# Multiplexer_8_to_1.net
KiCad netlist of a schematic drawn in Altium Designer
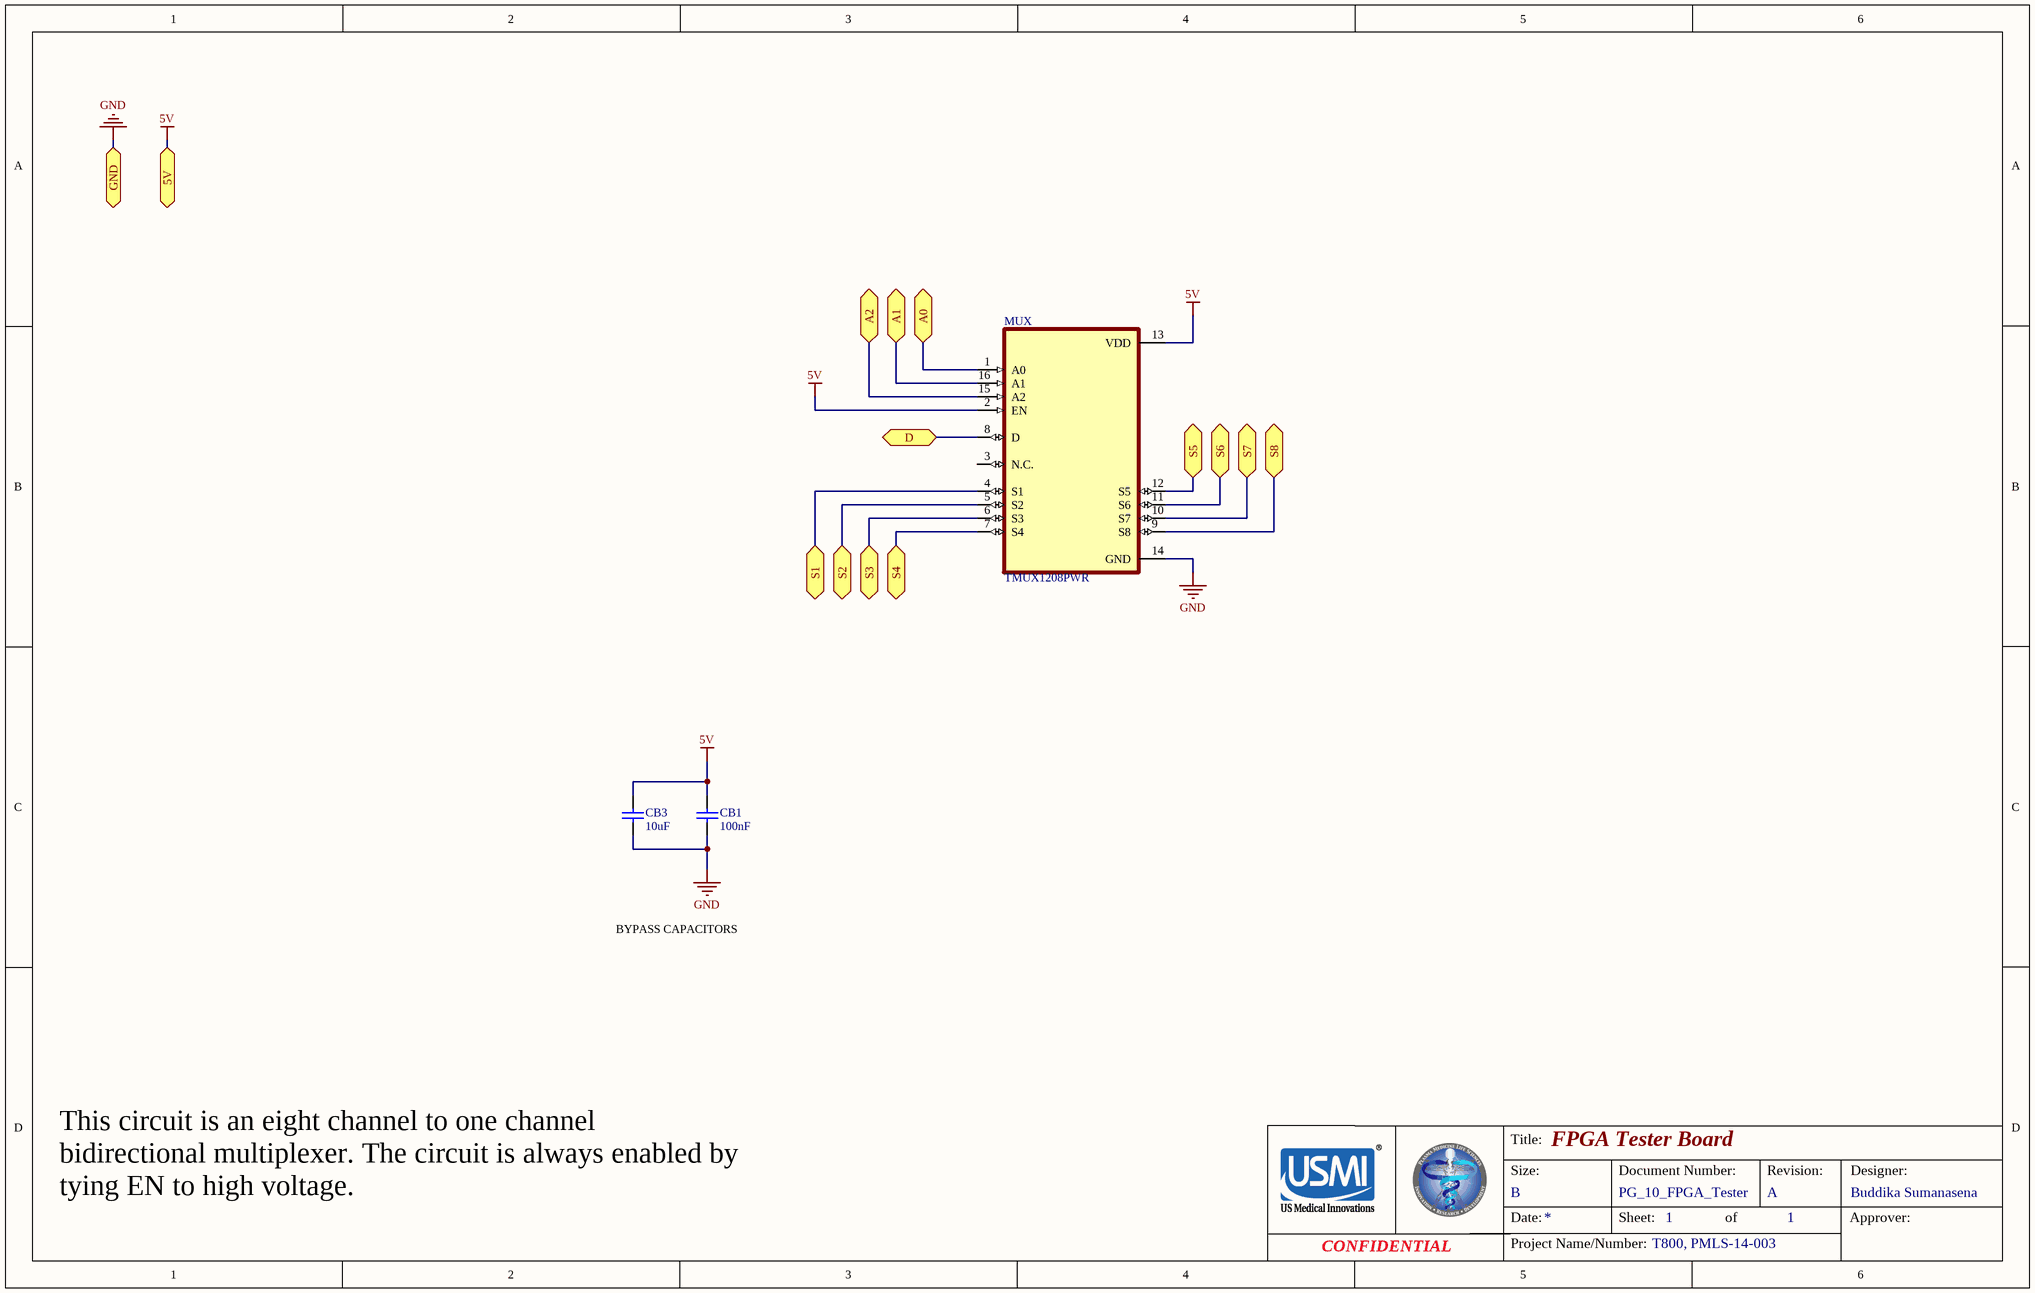
[diagram p0: Multiplexer_8_to_1.SchDoc]

(export (version "E")
  (design (tool "Eeschema 10.0.6"))
  (components
    (comp (ref "CB1")
      (value "100nF")
      (footprint "0805c")
      (description "Capacitor")
      (fields (field (name "PUBLISHER") "Altium Limited"))
      (libsource (lib "Buddika Miscellaneous Devices") (part "Cap"))
    )
    (comp (ref "CB3")
      (value "10uF")
      (footprint "1206c")
      (description "Capacitor")
      (fields (field (name "PUBLISHER") "Altium Limited"))
      (libsource (lib "Buddika Miscellaneous Devices") (part "Cap"))
    )
    (comp (ref "MUX")
      (value "TMUX1208PWR")
      (footprint "SOP65P640X120-16N")
      (description "5-V, 8:1, 1-channel general-purpose analog multiplexer with 1.8-V input logic 16-TSSOP -40 to 125")
      (fields (field (name "MF") "Texas Instruments"))
      (libsource (lib "TMUX1208PWR") (part "TMUX1208PWR"))
    )
  )
  (nets
    (net (code "1") (name "/A0") (class "Default")
      (node (ref "MUX") (pin "1") (pinfunction "A0_1") (pintype "input"))
    )
    (net (code "2") (name "/A1") (class "Default")
      (node (ref "MUX") (pin "16") (pinfunction "A1_16") (pintype "input"))
    )
    (net (code "3") (name "/A2") (class "Default")
      (node (ref "MUX") (pin "15") (pinfunction "A2_15") (pintype "input"))
    )
    (net (code "4") (name "/D") (class "Default")
      (node (ref "MUX") (pin "8") (pinfunction "D_8") (pintype "bidirectional"))
    )
    (net (code "5") (name "/S1") (class "Default")
      (node (ref "MUX") (pin "4") (pinfunction "S1_4") (pintype "bidirectional"))
    )
    (net (code "6") (name "/S2") (class "Default")
      (node (ref "MUX") (pin "5") (pinfunction "S2_5") (pintype "bidirectional"))
    )
    (net (code "7") (name "/S3") (class "Default")
      (node (ref "MUX") (pin "6") (pinfunction "S3_6") (pintype "bidirectional"))
    )
    (net (code "8") (name "/S4") (class "Default")
      (node (ref "MUX") (pin "7") (pinfunction "S4_7") (pintype "bidirectional"))
    )
    (net (code "9") (name "/S5") (class "Default")
      (node (ref "MUX") (pin "12") (pinfunction "S5_12") (pintype "bidirectional"))
    )
    (net (code "10") (name "/S6") (class "Default")
      (node (ref "MUX") (pin "11") (pinfunction "S6_11") (pintype "bidirectional"))
    )
    (net (code "11") (name "/S7") (class "Default")
      (node (ref "MUX") (pin "10") (pinfunction "S7_10") (pintype "bidirectional"))
    )
    (net (code "12") (name "/S8") (class "Default")
      (node (ref "MUX") (pin "9") (pinfunction "S8_9") (pintype "bidirectional"))
    )
    (net (code "13") (name "5V") (class "Default")
      (node (ref "CB1") (pin "2") (pinfunction "2_2") (pintype "passive"))
      (node (ref "CB3") (pin "2") (pinfunction "2_2") (pintype "passive"))
      (node (ref "MUX") (pin "13") (pinfunction "VDD_13") (pintype "power_in"))
      (node (ref "MUX") (pin "2") (pinfunction "EN_2") (pintype "input"))
    )
    (net (code "14") (name "GND") (class "Default")
      (node (ref "CB1") (pin "1") (pinfunction "1_1") (pintype "passive"))
      (node (ref "CB3") (pin "1") (pinfunction "1_1") (pintype "passive"))
      (node (ref "MUX") (pin "14") (pinfunction "GND_14") (pintype "power_in"))
    )
    (net (code "15") (name "unconnected-(MUX-N.C.-Pad3)") (class "Default")
      (node (ref "MUX") (pin "3") (pinfunction "N.C._3") (pintype "bidirectional"))
    )
  )
)
